# Connectors.net
KiCad netlist of a schematic drawn in Altium Designer
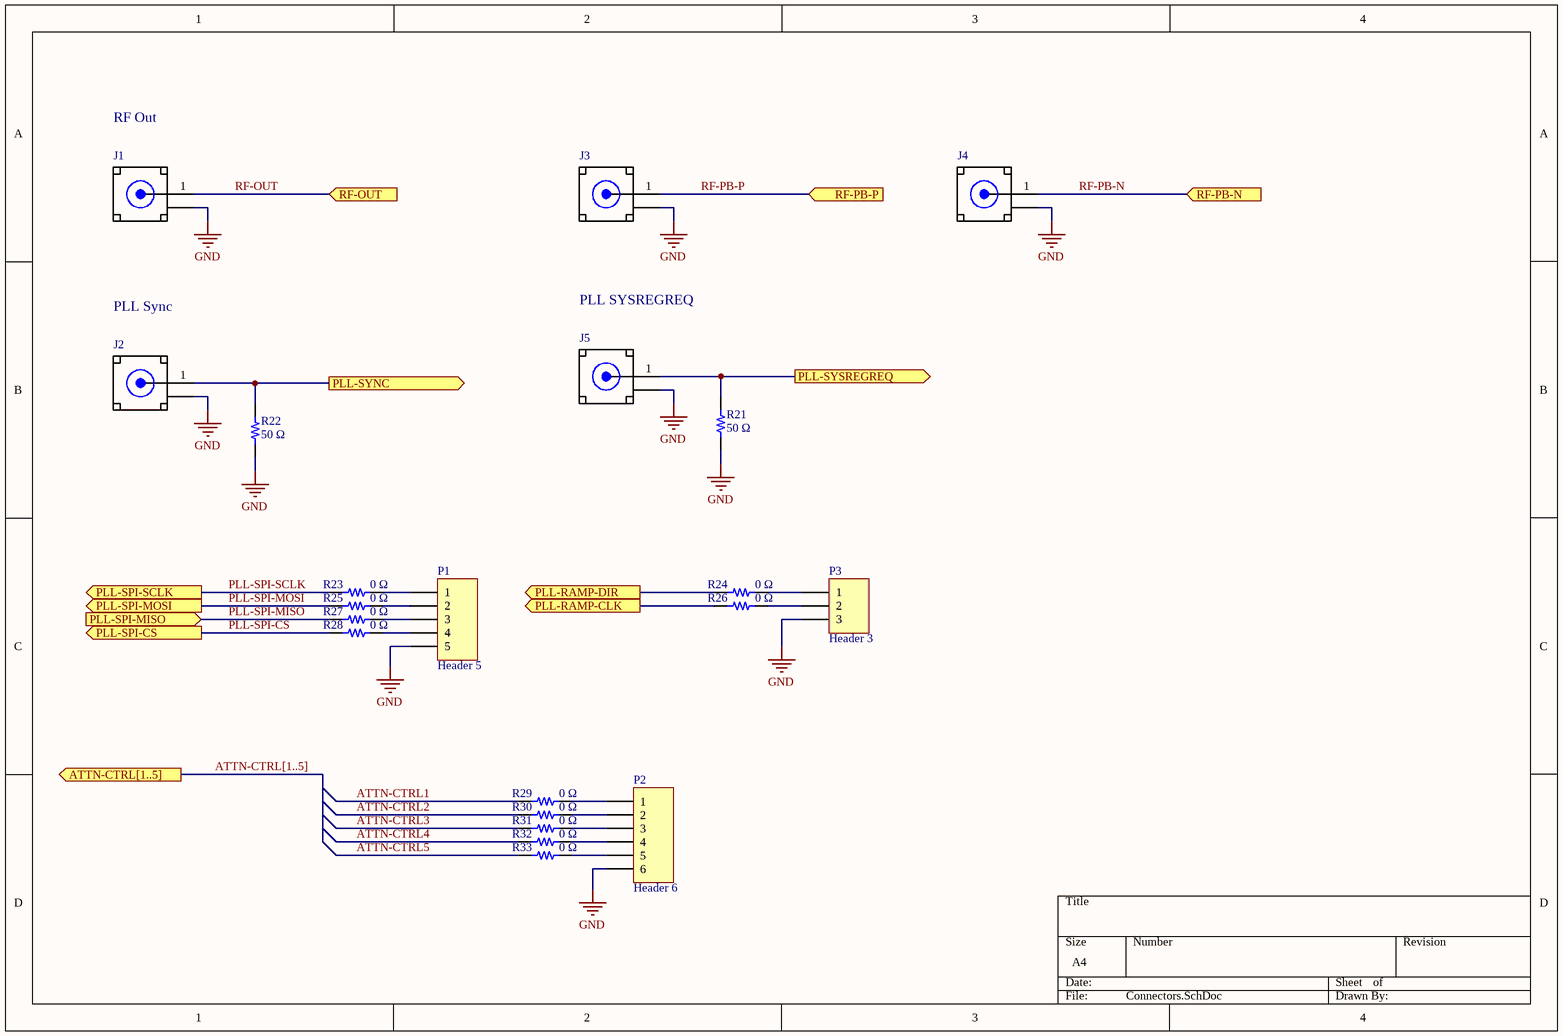
[diagram p0: Connectors.SchDoc]

(export (version "E")
  (design (tool "Eeschema 10.0.6"))
  (components
    (comp (ref "J1")
      (value "SMA-J-P-H-ST-EM1")
      (footprint "SAMTEC SMA-J-P-H-ST-EM1")
      (description "CONN SMA JACK STR 50OHM EDGE MNT")
      (fields (field (name "MANUFACTURER") "Samtec Inc."))
      (libsource (lib "Generic Altium Database") (part "SAMTEC SMA-J-P-H-ST-EM1"))
    )
    (comp (ref "J2")
      (value "SMA-J-P-H-ST-EM1")
      (footprint "SAMTEC SMA-J-P-H-ST-EM1")
      (description "CONN SMA JACK STR 50OHM EDGE MNT")
      (fields (field (name "MANUFACTURER") "Samtec Inc."))
      (libsource (lib "Generic Altium Database") (part "SAMTEC SMA-J-P-H-ST-EM1"))
    )
    (comp (ref "J3")
      (value "SMA-J-P-H-ST-EM1")
      (footprint "SAMTEC SMA-J-P-H-ST-EM1")
      (description "CONN SMA JACK STR 50OHM EDGE MNT")
      (fields (field (name "MANUFACTURER") "Samtec Inc."))
      (libsource (lib "Generic Altium Database") (part "SAMTEC SMA-J-P-H-ST-EM1"))
    )
    (comp (ref "J4")
      (value "SMA-J-P-H-ST-EM1")
      (footprint "SAMTEC SMA-J-P-H-ST-EM1")
      (description "CONN SMA JACK STR 50OHM EDGE MNT")
      (fields (field (name "MANUFACTURER") "Samtec Inc."))
      (libsource (lib "Generic Altium Database") (part "SAMTEC SMA-J-P-H-ST-EM1"))
    )
    (comp (ref "J5")
      (value "SMA-J-P-H-ST-EM1")
      (footprint "SAMTEC SMA-J-P-H-ST-EM1")
      (description "CONN SMA JACK STR 50OHM EDGE MNT")
      (fields (field (name "MANUFACTURER") "Samtec Inc."))
      (libsource (lib "Generic Altium Database") (part "SAMTEC SMA-J-P-H-ST-EM1"))
    )
    (comp (ref "P1")
      (value "Header 5")
      (footprint "HDR1X5")
      (description "Header, 5-Pin")
      (fields (field (name "PUBLISHER") "Altium Limited"))
      (libsource (lib "Miscellaneous Connectors") (part "Header 5"))
    )
    (comp (ref "P2")
      (value "Header 6")
      (footprint "HDR1X6")
      (description "Header, 6-Pin")
      (fields (field (name "PUBLISHER") "Altium Limited"))
      (libsource (lib "Miscellaneous Connectors") (part "Header 6"))
    )
    (comp (ref "P3")
      (value "Header 3")
      (footprint "HDR1X3")
      (description "Header, 3-Pin")
      (fields (field (name "PUBLISHER") "Altium Limited"))
      (libsource (lib "Miscellaneous Connectors") (part "Header 3"))
    )
    (comp (ref "R21")
      (value "50 Ω")
      (footprint "RES 0603_1608")
      (description "RES SMD 50 OHM 2% 1.5W 0603")
      (fields (field (name "PART NUMBER") "RCP0603W50R0GEB") (field (name "MANUFACTURER") "Vishay Dale"))
      (libsource (lib "Generic Altium Database") (part "Resistor"))
    )
    (comp (ref "R22")
      (value "50 Ω")
      (footprint "RES 0603_1608")
      (description "RES SMD 50 OHM 2% 1.5W 0603")
      (fields (field (name "PART NUMBER") "RCP0603W50R0GEB") (field (name "MANUFACTURER") "Vishay Dale"))
      (libsource (lib "Generic Altium Database") (part "Resistor"))
    )
    (comp (ref "R23")
      (value "0 Ω")
      (footprint "RES 0402_1005")
      (description "RES 0 OHM JUMPER 1/16W 0402")
      (fields (field (name "PART NUMBER") "CR0402-J/-000GAS") (field (name "MANUFACTURER") "Bourns Inc."))
      (libsource (lib "Generic Altium Database") (part "Resistor"))
    )
    (comp (ref "R24")
      (value "0 Ω")
      (footprint "RES 0402_1005")
      (description "RES 0 OHM JUMPER 1/16W 0402")
      (fields (field (name "PART NUMBER") "CR0402-J/-000GAS") (field (name "MANUFACTURER") "Bourns Inc."))
      (libsource (lib "Generic Altium Database") (part "Resistor"))
    )
    (comp (ref "R25")
      (value "0 Ω")
      (footprint "RES 0402_1005")
      (description "RES 0 OHM JUMPER 1/16W 0402")
      (fields (field (name "PART NUMBER") "CR0402-J/-000GAS") (field (name "MANUFACTURER") "Bourns Inc."))
      (libsource (lib "Generic Altium Database") (part "Resistor"))
    )
    (comp (ref "R26")
      (value "0 Ω")
      (footprint "RES 0402_1005")
      (description "RES 0 OHM JUMPER 1/16W 0402")
      (fields (field (name "PART NUMBER") "CR0402-J/-000GAS") (field (name "MANUFACTURER") "Bourns Inc."))
      (libsource (lib "Generic Altium Database") (part "Resistor"))
    )
    (comp (ref "R27")
      (value "0 Ω")
      (footprint "RES 0402_1005")
      (description "RES 0 OHM JUMPER 1/16W 0402")
      (fields (field (name "PART NUMBER") "CR0402-J/-000GAS") (field (name "MANUFACTURER") "Bourns Inc."))
      (libsource (lib "Generic Altium Database") (part "Resistor"))
    )
    (comp (ref "R28")
      (value "0 Ω")
      (footprint "RES 0402_1005")
      (description "RES 0 OHM JUMPER 1/16W 0402")
      (fields (field (name "PART NUMBER") "CR0402-J/-000GAS") (field (name "MANUFACTURER") "Bourns Inc."))
      (libsource (lib "Generic Altium Database") (part "Resistor"))
    )
    (comp (ref "R29")
      (value "0 Ω")
      (footprint "RES 0402_1005")
      (description "RES 0 OHM JUMPER 1/16W 0402")
      (fields (field (name "PART NUMBER") "CR0402-J/-000GAS") (field (name "MANUFACTURER") "Bourns Inc."))
      (libsource (lib "Generic Altium Database") (part "Resistor"))
    )
    (comp (ref "R30")
      (value "0 Ω")
      (footprint "RES 0402_1005")
      (description "RES 0 OHM JUMPER 1/16W 0402")
      (fields (field (name "PART NUMBER") "CR0402-J/-000GAS") (field (name "MANUFACTURER") "Bourns Inc."))
      (libsource (lib "Generic Altium Database") (part "Resistor"))
    )
    (comp (ref "R31")
      (value "0 Ω")
      (footprint "RES 0402_1005")
      (description "RES 0 OHM JUMPER 1/16W 0402")
      (fields (field (name "PART NUMBER") "CR0402-J/-000GAS") (field (name "MANUFACTURER") "Bourns Inc."))
      (libsource (lib "Generic Altium Database") (part "Resistor"))
    )
    (comp (ref "R32")
      (value "0 Ω")
      (footprint "RES 0402_1005")
      (description "RES 0 OHM JUMPER 1/16W 0402")
      (fields (field (name "PART NUMBER") "CR0402-J/-000GAS") (field (name "MANUFACTURER") "Bourns Inc."))
      (libsource (lib "Generic Altium Database") (part "Resistor"))
    )
    (comp (ref "R33")
      (value "0 Ω")
      (footprint "RES 0402_1005")
      (description "RES 0 OHM JUMPER 1/16W 0402")
      (fields (field (name "PART NUMBER") "CR0402-J/-000GAS") (field (name "MANUFACTURER") "Bourns Inc."))
      (libsource (lib "Generic Altium Database") (part "Resistor"))
    )
  )
  (nets
    (net (code "1") (name "/ATTN-CTRL1") (class "Default")
      (node (ref "R29") (pin "1") (pinfunction "1_1") (pintype "passive"))
    )
    (net (code "2") (name "/ATTN-CTRL2") (class "Default")
      (node (ref "R30") (pin "1") (pinfunction "1_1") (pintype "passive"))
    )
    (net (code "3") (name "/ATTN-CTRL3") (class "Default")
      (node (ref "R31") (pin "1") (pinfunction "1_1") (pintype "passive"))
    )
    (net (code "4") (name "/ATTN-CTRL4") (class "Default")
      (node (ref "R32") (pin "1") (pinfunction "1_1") (pintype "passive"))
    )
    (net (code "5") (name "/ATTN-CTRL5") (class "Default")
      (node (ref "R33") (pin "1") (pinfunction "1_1") (pintype "passive"))
    )
    (net (code "7") (name "/PLL-RAMP-CLK") (class "Default")
      (node (ref "R26") (pin "1") (pinfunction "1_1") (pintype "passive"))
    )
    (net (code "8") (name "/PLL-RAMP-DIR") (class "Default")
      (node (ref "R24") (pin "1") (pinfunction "1_1") (pintype "passive"))
    )
    (net (code "9") (name "/PLL-SPI-CS") (class "Default")
      (node (ref "R28") (pin "1") (pinfunction "1_1") (pintype "passive"))
    )
    (net (code "10") (name "/PLL-SPI-MISO") (class "Default")
      (node (ref "R27") (pin "1") (pinfunction "1_1") (pintype "passive"))
    )
    (net (code "11") (name "/PLL-SPI-MOSI") (class "Default")
      (node (ref "R25") (pin "1") (pinfunction "1_1") (pintype "passive"))
    )
    (net (code "12") (name "/PLL-SPI-SCLK") (class "Default")
      (node (ref "R23") (pin "1") (pinfunction "1_1") (pintype "passive"))
    )
    (net (code "13") (name "/PLL-SYNC") (class "Default")
      (node (ref "J2") (pin "1") (pinfunction "SIGNAL_1") (pintype "passive"))
      (node (ref "R22") (pin "1") (pinfunction "1_1") (pintype "passive"))
    )
    (net (code "14") (name "/PLL-SYSREGREQ") (class "Default")
      (node (ref "J5") (pin "1") (pinfunction "SIGNAL_1") (pintype "passive"))
      (node (ref "R21") (pin "1") (pinfunction "1_1") (pintype "passive"))
    )
    (net (code "15") (name "/RF-OUT") (class "Default")
      (node (ref "J1") (pin "1") (pinfunction "SIGNAL_1") (pintype "passive"))
    )
    (net (code "16") (name "/RF-PB-N") (class "Default")
      (node (ref "J4") (pin "1") (pinfunction "SIGNAL_1") (pintype "passive"))
    )
    (net (code "17") (name "/RF-PB-P") (class "Default")
      (node (ref "J3") (pin "1") (pinfunction "SIGNAL_1") (pintype "passive"))
    )
    (net (code "18") (name "GND") (class "Default")
      (node (ref "J1") (pin "2") (pinfunction "GND_2") (pintype "power_in"))
      (node (ref "J2") (pin "2") (pinfunction "GND_2") (pintype "power_in"))
      (node (ref "J3") (pin "2") (pinfunction "GND_2") (pintype "power_in"))
      (node (ref "J4") (pin "2") (pinfunction "GND_2") (pintype "power_in"))
      (node (ref "J5") (pin "2") (pinfunction "GND_2") (pintype "power_in"))
      (node (ref "P1") (pin "5") (pinfunction "5_5") (pintype "passive"))
      (node (ref "P2") (pin "6") (pinfunction "6_6") (pintype "passive"))
      (node (ref "P3") (pin "3") (pinfunction "3_3") (pintype "passive"))
      (node (ref "R21") (pin "2") (pinfunction "2_2") (pintype "passive"))
      (node (ref "R22") (pin "2") (pinfunction "2_2") (pintype "passive"))
    )
    (net (code "19") (name "Net-(P1-Pad1)") (class "Default")
      (node (ref "P1") (pin "1") (pinfunction "1_1") (pintype "passive"))
      (node (ref "R23") (pin "2") (pinfunction "2_2") (pintype "passive"))
    )
    (net (code "20") (name "Net-(P1-Pad2)") (class "Default")
      (node (ref "P1") (pin "2") (pinfunction "2_2") (pintype "passive"))
      (node (ref "R25") (pin "2") (pinfunction "2_2") (pintype "passive"))
    )
    (net (code "21") (name "Net-(P1-Pad3)") (class "Default")
      (node (ref "P1") (pin "3") (pinfunction "3_3") (pintype "passive"))
      (node (ref "R27") (pin "2") (pinfunction "2_2") (pintype "passive"))
    )
    (net (code "22") (name "Net-(P1-Pad4)") (class "Default")
      (node (ref "P1") (pin "4") (pinfunction "4_4") (pintype "passive"))
      (node (ref "R28") (pin "2") (pinfunction "2_2") (pintype "passive"))
    )
    (net (code "23") (name "Net-(P2-Pad1)") (class "Default")
      (node (ref "P2") (pin "1") (pinfunction "1_1") (pintype "passive"))
      (node (ref "R29") (pin "2") (pinfunction "2_2") (pintype "passive"))
    )
    (net (code "24") (name "Net-(P2-Pad2)") (class "Default")
      (node (ref "P2") (pin "2") (pinfunction "2_2") (pintype "passive"))
      (node (ref "R30") (pin "2") (pinfunction "2_2") (pintype "passive"))
    )
    (net (code "25") (name "Net-(P2-Pad3)") (class "Default")
      (node (ref "P2") (pin "3") (pinfunction "3_3") (pintype "passive"))
      (node (ref "R31") (pin "2") (pinfunction "2_2") (pintype "passive"))
    )
    (net (code "26") (name "Net-(P2-Pad4)") (class "Default")
      (node (ref "P2") (pin "4") (pinfunction "4_4") (pintype "passive"))
      (node (ref "R32") (pin "2") (pinfunction "2_2") (pintype "passive"))
    )
    (net (code "27") (name "Net-(P2-Pad5)") (class "Default")
      (node (ref "P2") (pin "5") (pinfunction "5_5") (pintype "passive"))
      (node (ref "R33") (pin "2") (pinfunction "2_2") (pintype "passive"))
    )
    (net (code "28") (name "Net-(P3-Pad1)") (class "Default")
      (node (ref "P3") (pin "1") (pinfunction "1_1") (pintype "passive"))
      (node (ref "R24") (pin "2") (pinfunction "2_2") (pintype "passive"))
    )
    (net (code "29") (name "Net-(P3-Pad2)") (class "Default")
      (node (ref "P3") (pin "2") (pinfunction "2_2") (pintype "passive"))
      (node (ref "R26") (pin "2") (pinfunction "2_2") (pintype "passive"))
    )
  )
)
